# STM32_ADC.net
KiCad netlist of a schematic drawn in Altium Designer
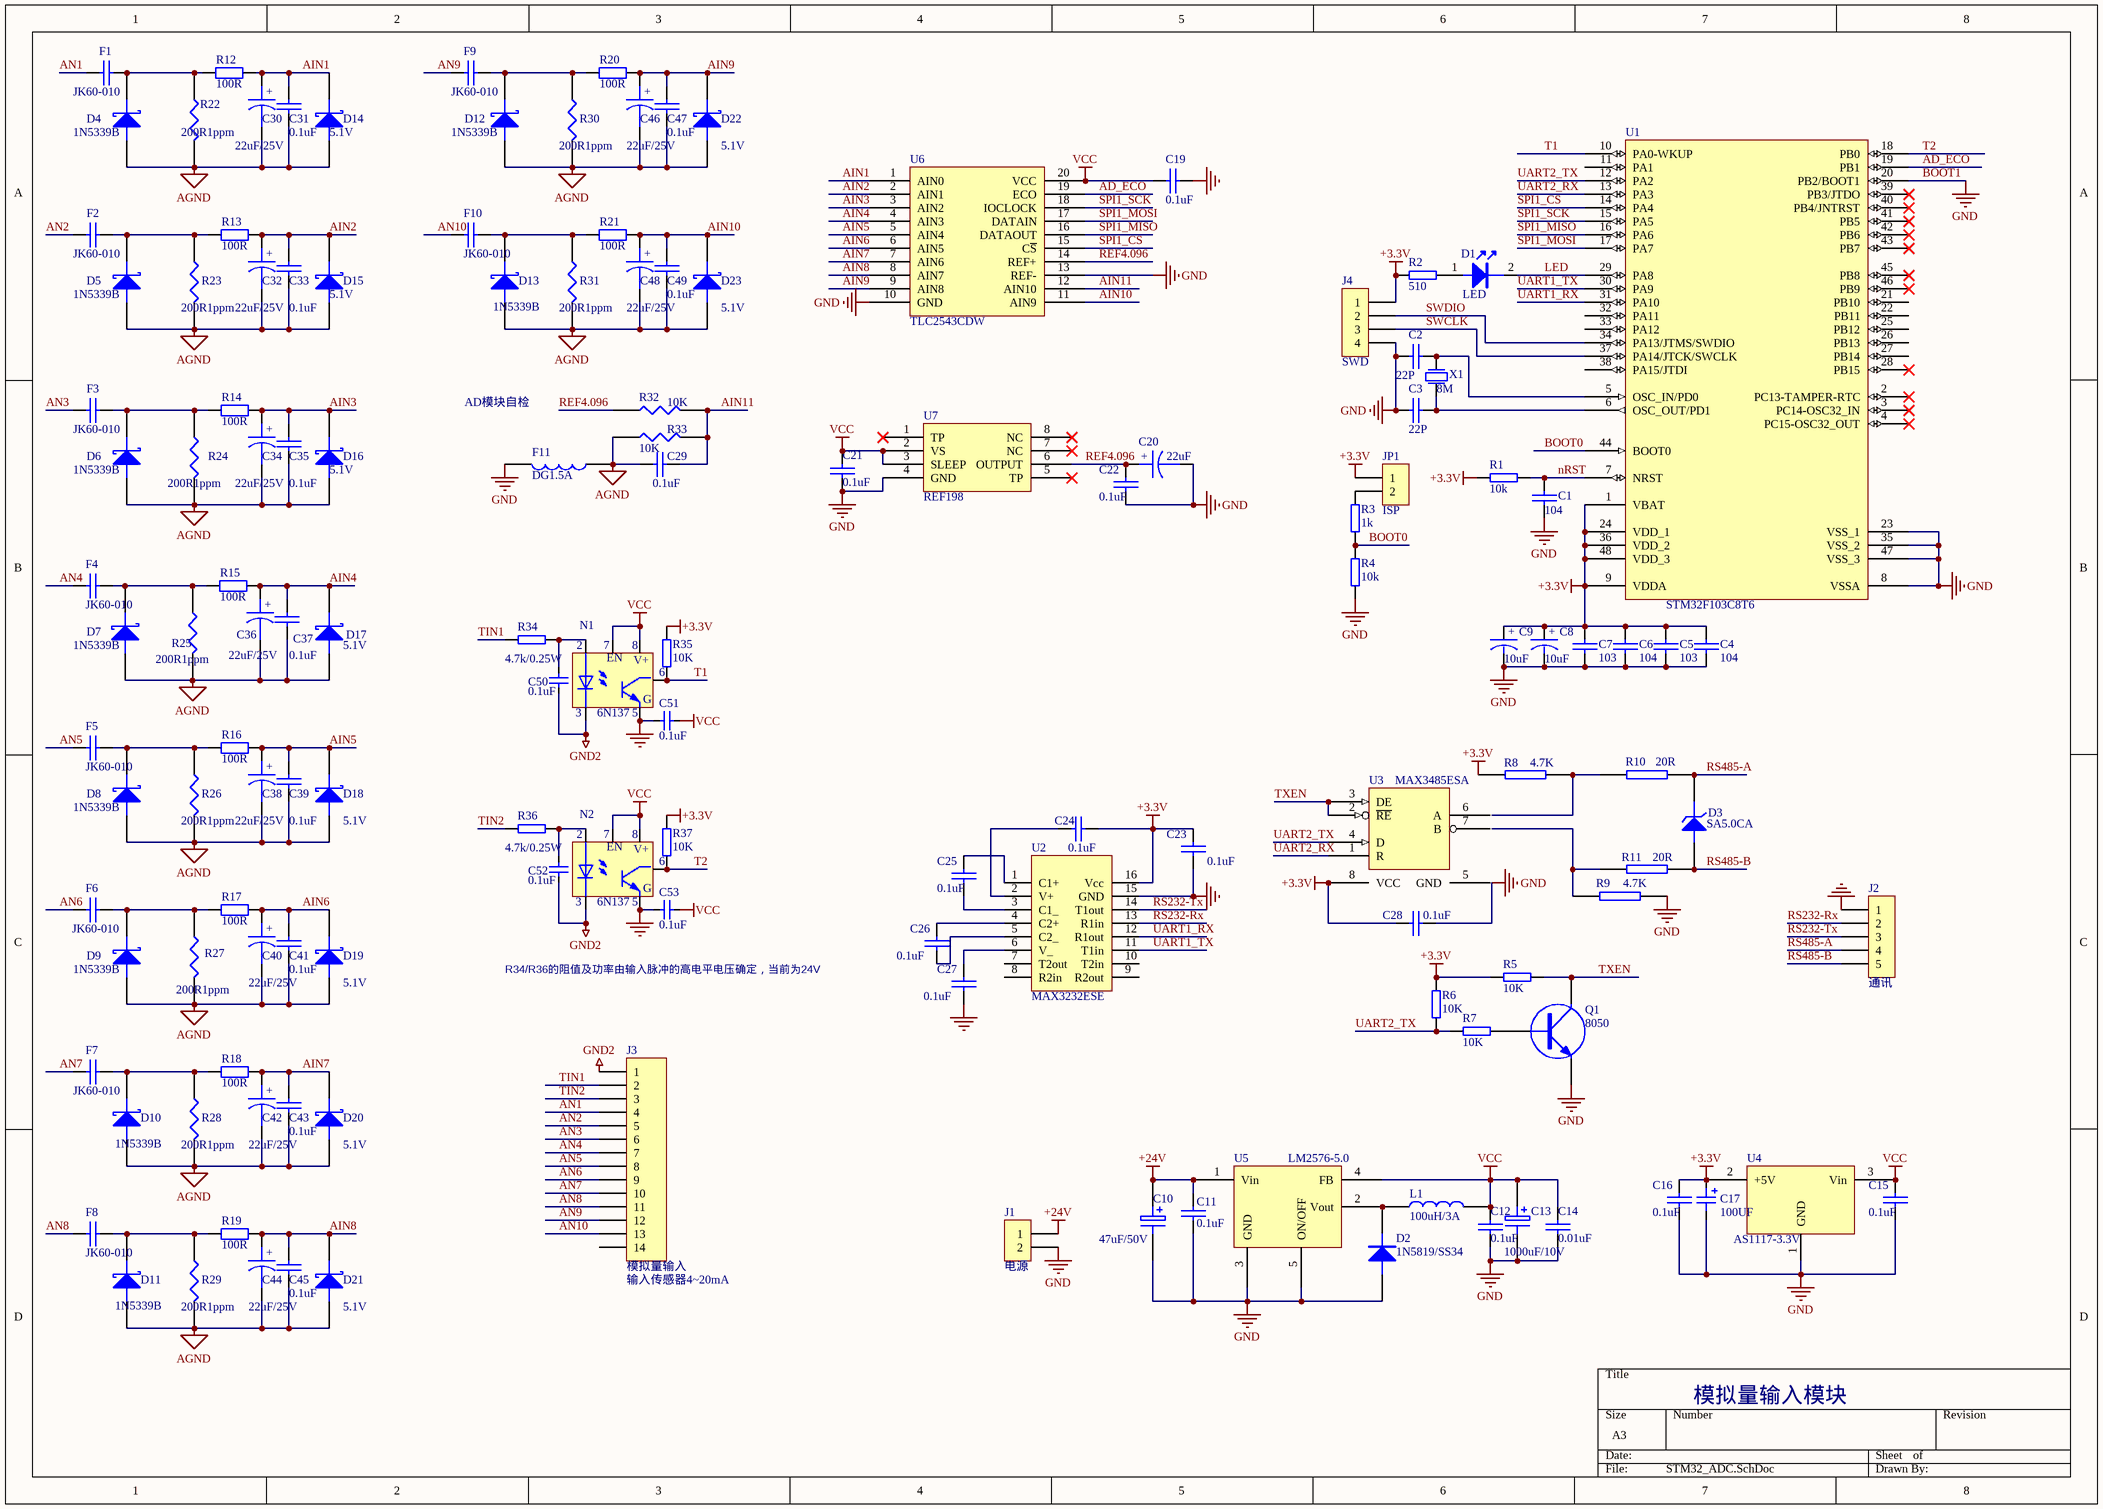
[diagram p0: STM32_ADC.SchDoc]

(export (version "E")
  (design (tool "Eeschema 10.0.6"))
  (components
    (comp (ref "C1")
      (value "104")
      (footprint "0805")
      (description "Capacitor")
      (libsource (lib "") (part "CAP_2"))
    )
    (comp (ref "C2")
      (value "22P")
      (footprint "0805")
      (description "Capacitor")
      (libsource (lib "*") (part "CAP"))
    )
    (comp (ref "C3")
      (value "22P")
      (footprint "0805")
      (description "Capacitor")
      (libsource (lib "*") (part "CAP"))
    )
    (comp (ref "C4")
      (value "104")
      (footprint "0805")
      (description "Capacitor")
      (libsource (lib "") (part "CAP_2"))
    )
    (comp (ref "C5")
      (value "103")
      (footprint "0805")
      (description "Capacitor")
      (libsource (lib "") (part "CAP_2"))
    )
    (comp (ref "C6")
      (value "104")
      (footprint "0805")
      (description "Capacitor")
      (libsource (lib "") (part "CAP_2"))
    )
    (comp (ref "C7")
      (value "103")
      (footprint "0805")
      (description "Capacitor")
      (libsource (lib "") (part "CAP_2"))
    )
    (comp (ref "C8")
      (value "10uF")
      (footprint "1210(+)")
      (description "Capacitor")
      (libsource (lib "2400原理图库") (part "CAPACITOR POL_1"))
    )
    (comp (ref "C9")
      (value "10uF")
      (footprint "1210(+)")
      (description "Capacitor")
      (libsource (lib "2400原理图库") (part "CAPACITOR POL_1"))
    )
    (comp (ref "C10")
      (value "47uF/50V")
      (footprint "ROND-0.2")
      (description "Electrolytic Capacitor")
      (libsource (lib "*") (part "ELECTRO1"))
    )
    (comp (ref "C11")
      (value "0.1uF")
      (footprint "0805")
      (description "Capacitor")
      (libsource (lib "") (part "CAP_1"))
    )
    (comp (ref "C12")
      (value "0.1uF")
      (footprint "0805")
      (description "Capacitor")
      (libsource (lib "") (part "CAP_1"))
    )
    (comp (ref "C13")
      (value "1000uF/10V")
      (footprint "DR10*10")
      (description "Electrolytic Capacitor")
      (libsource (lib "*") (part "ELECTRO1"))
    )
    (comp (ref "C14")
      (value "0.01uF")
      (footprint "0805")
      (description "Capacitor")
      (libsource (lib "") (part "CAP_1"))
    )
    (comp (ref "C15")
      (value "0.1uF")
      (footprint "0805")
      (description "Capacitor")
      (libsource (lib "*") (part "CAP"))
    )
    (comp (ref "C16")
      (value "0.1uF")
      (footprint "0805")
      (description "Capacitor")
      (libsource (lib "*") (part "CAP"))
    )
    (comp (ref "C17") (value "100UF") (footprint "2220-1") (libsource (lib "*") (part "CD")))
    (comp (ref "C19")
      (value "0.1uF")
      (footprint "0805")
      (description "Capacitor")
      (libsource (lib "*") (part "CAP"))
    )
    (comp (ref "C20")
      (value "22uF")
      (footprint "1210(+)")
      (description "Capacitor")
      (libsource (lib "*") (part "CAPACITOR POL"))
    )
    (comp (ref "C21")
      (value "0.1uF")
      (footprint "0805")
      (description "Capacitor")
      (libsource (lib "*") (part "CAP"))
    )
    (comp (ref "C22")
      (value "0.1uF")
      (footprint "0805")
      (description "Capacitor")
      (libsource (lib "*") (part "CAP"))
    )
    (comp (ref "C23")
      (value "0.1uF")
      (footprint "0805")
      (description "Capacitor")
      (libsource (lib "*") (part "CAP"))
    )
    (comp (ref "C24")
      (value "0.1uF")
      (footprint "0805")
      (description "Capacitor")
      (libsource (lib "*") (part "CAP"))
    )
    (comp (ref "C25")
      (value "0.1uF")
      (footprint "0805")
      (description "Capacitor")
      (libsource (lib "*") (part "CAP"))
    )
    (comp (ref "C26")
      (value "0.1uF")
      (footprint "0805")
      (description "Capacitor")
      (libsource (lib "*") (part "CAP"))
    )
    (comp (ref "C27")
      (value "0.1uF")
      (footprint "0805")
      (description "Capacitor")
      (libsource (lib "*") (part "CAP"))
    )
    (comp (ref "C28")
      (value "0.1uF")
      (footprint "0805")
      (description "Capacitor")
      (libsource (lib "*") (part "CAP"))
    )
    (comp (ref "C29")
      (value "0.1uF")
      (footprint "0805")
      (description "Capacitor")
      (libsource (lib "*") (part "CAP"))
    )
    (comp (ref "C30")
      (value "22uF/25V")
      (footprint "1210(+)")
      (description "Capacitor")
      (libsource (lib "*") (part "CAPACITOR POL"))
    )
    (comp (ref "C31")
      (value "0.1uF")
      (footprint "0805")
      (description "Capacitor")
      (libsource (lib "*") (part "CAP"))
    )
    (comp (ref "C32")
      (value "22uF/25V")
      (footprint "1210(+)")
      (description "Capacitor")
      (libsource (lib "*") (part "CAPACITOR POL"))
    )
    (comp (ref "C33")
      (value "0.1uF")
      (footprint "0805")
      (description "Capacitor")
      (libsource (lib "*") (part "CAP"))
    )
    (comp (ref "C34")
      (value "22uF/25V")
      (footprint "1210(+)")
      (description "Capacitor")
      (libsource (lib "*") (part "CAPACITOR POL"))
    )
    (comp (ref "C35")
      (value "0.1uF")
      (footprint "0805")
      (description "Capacitor")
      (libsource (lib "*") (part "CAP"))
    )
    (comp (ref "C36")
      (value "22uF/25V")
      (footprint "1210(+)")
      (description "Capacitor")
      (libsource (lib "*") (part "CAPACITOR POL"))
    )
    (comp (ref "C37")
      (value "0.1uF")
      (footprint "0805")
      (description "Capacitor")
      (libsource (lib "*") (part "CAP"))
    )
    (comp (ref "C38")
      (value "22uF/25V")
      (footprint "1210(+)")
      (description "Capacitor")
      (libsource (lib "*") (part "CAPACITOR POL"))
    )
    (comp (ref "C39")
      (value "0.1uF")
      (footprint "0805")
      (description "Capacitor")
      (libsource (lib "*") (part "CAP"))
    )
    (comp (ref "C40")
      (value "22uF/25V")
      (footprint "1210(+)")
      (description "Capacitor")
      (libsource (lib "*") (part "CAPACITOR POL"))
    )
    (comp (ref "C41")
      (value "0.1uF")
      (footprint "0805")
      (description "Capacitor")
      (libsource (lib "*") (part "CAP"))
    )
    (comp (ref "C42")
      (value "22uF/25V")
      (footprint "1210(+)")
      (description "Capacitor")
      (libsource (lib "*") (part "CAPACITOR POL"))
    )
    (comp (ref "C43")
      (value "0.1uF")
      (footprint "0805")
      (description "Capacitor")
      (libsource (lib "*") (part "CAP"))
    )
    (comp (ref "C44")
      (value "22uF/25V")
      (footprint "1210(+)")
      (description "Capacitor")
      (libsource (lib "*") (part "CAPACITOR POL"))
    )
    (comp (ref "C45")
      (value "0.1uF")
      (footprint "0805")
      (description "Capacitor")
      (libsource (lib "*") (part "CAP"))
    )
    (comp (ref "C46")
      (value "22uF/25V")
      (footprint "1210(+)")
      (description "Capacitor")
      (libsource (lib "*") (part "CAPACITOR POL"))
    )
    (comp (ref "C47")
      (value "0.1uF")
      (footprint "0805")
      (description "Capacitor")
      (libsource (lib "*") (part "CAP"))
    )
    (comp (ref "C48")
      (value "22uF/25V")
      (footprint "1210(+)")
      (description "Capacitor")
      (libsource (lib "*") (part "CAPACITOR POL"))
    )
    (comp (ref "C49")
      (value "0.1uF")
      (footprint "0805")
      (description "Capacitor")
      (libsource (lib "*") (part "CAP"))
    )
    (comp (ref "C50") (value "0.1uF") (footprint "0805") (libsource (lib "*") (part "C")))
    (comp (ref "C51") (value "0.1uF") (footprint "0805") (libsource (lib "*") (part "C")))
    (comp (ref "C52") (value "0.1uF") (footprint "0805") (libsource (lib "*") (part "C")))
    (comp (ref "C53") (value "0.1uF") (footprint "0805") (libsource (lib "*") (part "C")))
    (comp (ref "D1") (value "LED") (footprint "0805") (libsource (lib "pro1") (part "LED")))
    (comp (ref "D2")
      (value "1N5819/SS34")
      (footprint "DIODE-2")
      (description "Diode")
      (libsource (lib "*") (part "DIODE"))
    )
    (comp (ref "D3")
      (value "SA5.0CA")
      (footprint "CON2_4A7")
      (description "Zener Diode")
      (libsource (lib "*") (part "ZENER3"))
    )
    (comp (ref "D4")
      (value "1N5339B")
      (footprint "DIODE-0.3")
      (description "Schottky Diode")
      (libsource (lib "*") (part "DIODE SCHOTTKY"))
    )
    (comp (ref "D5")
      (value "1N5339B")
      (footprint "DIODE-0.3")
      (description "Schottky Diode")
      (libsource (lib "*") (part "DIODE SCHOTTKY"))
    )
    (comp (ref "D6")
      (value "1N5339B")
      (footprint "DIODE-0.3")
      (description "Schottky Diode")
      (libsource (lib "*") (part "DIODE SCHOTTKY"))
    )
    (comp (ref "D7")
      (value "1N5339B")
      (footprint "DIODE-0.3")
      (description "Schottky Diode")
      (libsource (lib "*") (part "DIODE SCHOTTKY"))
    )
    (comp (ref "D8")
      (value "1N5339B")
      (footprint "DIODE-0.3")
      (description "Schottky Diode")
      (libsource (lib "*") (part "DIODE SCHOTTKY"))
    )
    (comp (ref "D9")
      (value "1N5339B")
      (footprint "DIODE-0.3")
      (description "Schottky Diode")
      (libsource (lib "*") (part "DIODE SCHOTTKY"))
    )
    (comp (ref "D10")
      (value "1N5339B")
      (footprint "DIODE-0.3")
      (description "Schottky Diode")
      (libsource (lib "*") (part "DIODE SCHOTTKY"))
    )
    (comp (ref "D11")
      (value "1N5339B")
      (footprint "DIODE-0.3")
      (description "Schottky Diode")
      (libsource (lib "*") (part "DIODE SCHOTTKY"))
    )
    (comp (ref "D12")
      (value "1N5339B")
      (footprint "DIODE-0.3")
      (description "Schottky Diode")
      (libsource (lib "*") (part "DIODE SCHOTTKY"))
    )
    (comp (ref "D13")
      (value "1N5339B")
      (footprint "DIODE-0.3")
      (description "Schottky Diode")
      (libsource (lib "*") (part "DIODE SCHOTTKY"))
    )
    (comp (ref "D14")
      (value "5.1V")
      (footprint "DIDO")
      (description "Schottky Diode")
      (libsource (lib "*") (part "DIODE SCHOTTKY"))
    )
    (comp (ref "D15")
      (value "5.1V")
      (footprint "DIDO")
      (description "Schottky Diode")
      (libsource (lib "*") (part "DIODE SCHOTTKY"))
    )
    (comp (ref "D16")
      (value "5.1V")
      (footprint "DIDO")
      (description "Schottky Diode")
      (libsource (lib "*") (part "DIODE SCHOTTKY"))
    )
    (comp (ref "D17")
      (value "5.1V")
      (footprint "DIDO")
      (description "Schottky Diode")
      (libsource (lib "*") (part "DIODE SCHOTTKY"))
    )
    (comp (ref "D18")
      (value "5.1V")
      (footprint "DIDO")
      (description "Schottky Diode")
      (libsource (lib "*") (part "DIODE SCHOTTKY"))
    )
    (comp (ref "D19")
      (value "5.1V")
      (footprint "DIDO")
      (description "Schottky Diode")
      (libsource (lib "*") (part "DIODE SCHOTTKY"))
    )
    (comp (ref "D20")
      (value "5.1V")
      (footprint "DIDO")
      (description "Schottky Diode")
      (libsource (lib "*") (part "DIODE SCHOTTKY"))
    )
    (comp (ref "D21")
      (value "5.1V")
      (footprint "DIDO")
      (description "Schottky Diode")
      (libsource (lib "*") (part "DIODE SCHOTTKY"))
    )
    (comp (ref "D22")
      (value "5.1V")
      (footprint "DIDO")
      (description "Schottky Diode")
      (libsource (lib "*") (part "DIODE SCHOTTKY"))
    )
    (comp (ref "D23")
      (value "5.1V")
      (footprint "DIDO")
      (description "Schottky Diode")
      (libsource (lib "*") (part "DIODE SCHOTTKY"))
    )
    (comp (ref "F1")
      (value "JK60-010")
      (footprint "RAD0.1")
      (description "Capacitor")
      (libsource (lib "*") (part "CAP"))
    )
    (comp (ref "F2")
      (value "JK60-010")
      (footprint "RAD0.1")
      (description "Capacitor")
      (libsource (lib "*") (part "CAP"))
    )
    (comp (ref "F3")
      (value "JK60-010")
      (footprint "RAD0.1")
      (description "Capacitor")
      (libsource (lib "*") (part "CAP"))
    )
    (comp (ref "F4")
      (value "JK60-010")
      (footprint "RAD0.1")
      (description "Capacitor")
      (libsource (lib "*") (part "CAP"))
    )
    (comp (ref "F5")
      (value "JK60-010")
      (footprint "RAD0.1")
      (description "Capacitor")
      (libsource (lib "*") (part "CAP"))
    )
    (comp (ref "F6")
      (value "JK60-010")
      (footprint "RAD0.1")
      (description "Capacitor")
      (libsource (lib "*") (part "CAP"))
    )
    (comp (ref "F7")
      (value "JK60-010")
      (footprint "RAD0.1")
      (description "Capacitor")
      (libsource (lib "*") (part "CAP"))
    )
    (comp (ref "F8")
      (value "JK60-010")
      (footprint "RAD0.1")
      (description "Capacitor")
      (libsource (lib "*") (part "CAP"))
    )
    (comp (ref "F9")
      (value "JK60-010")
      (footprint "RAD0.1")
      (description "Capacitor")
      (libsource (lib "*") (part "CAP"))
    )
    (comp (ref "F10")
      (value "JK60-010")
      (footprint "RAD0.1")
      (description "Capacitor")
      (libsource (lib "*") (part "CAP"))
    )
    (comp (ref "F11") (value "DG1.5A") (footprint "0805") (libsource (lib "*") (part "INDUCTOR1")))
    (comp (ref "J1")
      (value "电源")
      (footprint "CON2_5.08")
      (description "Connector")
      (libsource (lib "") (part "CON2_1"))
    )
    (comp (ref "J2")
      (value "通讯")
      (footprint "con5")
      (description "Connector")
      (libsource (lib "pro1") (part "CON5"))
    )
    (comp (ref "J3") (value "模拟量输入") (libsource (lib "pro1") (part "CON14")))
    (comp (ref "J4")
      (value "SWD")
      (footprint "CON4")
      (description "Connector")
      (libsource (lib "*") (part "CON4"))
    )
    (comp (ref "JP1")
      (value "ISP")
      (footprint "CON2_2")
      (description "Connector")
      (libsource (lib "pro1") (part "CON2"))
    )
    (comp (ref "L1") (value "100uH/3A") (footprint "DIANGAN1.5A") (libsource (lib "") (part "INDUCTOR1_1")))
    (comp (ref "N1") (value "6N137") (footprint "DIP8") (libsource (lib "*") (part "6N137")))
    (comp (ref "N2") (value "6N137") (footprint "DIP8") (libsource (lib "*") (part "6N137")))
    (comp (ref "Q1")
      (value "8050")
      (footprint "sot-23")
      (description "NPN Transistor")
      (libsource (lib "*") (part "NPN"))
    )
    (comp (ref "R1") (value "10k") (footprint "0805") (libsource (lib "") (part "RES1_1")))
    (comp (ref "R2") (value "510") (footprint "0805") (libsource (lib "") (part "RES1_1")))
    (comp (ref "R3") (value "1k") (footprint "0805") (libsource (lib "") (part "RES1_1")))
    (comp (ref "R4") (value "10k") (footprint "0805") (libsource (lib "") (part "RES1_1")))
    (comp (ref "R5") (value "10K") (footprint "0805") (libsource (lib "") (part "R_1")))
    (comp (ref "R6") (value "10K") (footprint "0805") (libsource (lib "") (part "RES1_1")))
    (comp (ref "R7") (value "10K") (footprint "0805") (libsource (lib "") (part "R_1")))
    (comp (ref "R8") (value "4.7K") (footprint "0805") (libsource (lib "*") (part "RES2")))
    (comp (ref "R9") (value "4.7K") (footprint "0805") (libsource (lib "*") (part "RES2")))
    (comp (ref "R10") (value "20R") (footprint "0805") (libsource (lib "*") (part "RES2")))
    (comp (ref "R11") (value "20R") (footprint "0805") (libsource (lib "*") (part "RES2")))
    (comp (ref "R12")
      (value "100R")
      (footprint "0805")
      (description "Resistor")
      (fields (field (name "PUBLISHER") "*"))
      (libsource (lib "*") (part "Res2"))
    )
    (comp (ref "R13")
      (value "100R")
      (footprint "0805")
      (description "Resistor")
      (fields (field (name "PUBLISHER") "*"))
      (libsource (lib "*") (part "Res2"))
    )
    (comp (ref "R14")
      (value "100R")
      (footprint "0805")
      (description "Resistor")
      (fields (field (name "PUBLISHER") "*"))
      (libsource (lib "*") (part "Res2"))
    )
    (comp (ref "R15")
      (value "100R")
      (footprint "0805")
      (description "Resistor")
      (fields (field (name "PUBLISHER") "*"))
      (libsource (lib "*") (part "Res2"))
    )
    (comp (ref "R16")
      (value "100R")
      (footprint "0805")
      (description "Resistor")
      (fields (field (name "PUBLISHER") "*"))
      (libsource (lib "*") (part "Res2"))
    )
    (comp (ref "R17")
      (value "100R")
      (footprint "0805")
      (description "Resistor")
      (fields (field (name "PUBLISHER") "*"))
      (libsource (lib "*") (part "Res2"))
    )
    (comp (ref "R18")
      (value "100R")
      (footprint "0805")
      (description "Resistor")
      (fields (field (name "PUBLISHER") "*"))
      (libsource (lib "*") (part "Res2"))
    )
    (comp (ref "R19")
      (value "100R")
      (footprint "0805")
      (description "Resistor")
      (fields (field (name "PUBLISHER") "*"))
      (libsource (lib "*") (part "Res2"))
    )
    (comp (ref "R20")
      (value "100R")
      (footprint "0805")
      (description "Resistor")
      (fields (field (name "PUBLISHER") "*"))
      (libsource (lib "*") (part "Res2"))
    )
    (comp (ref "R21")
      (value "100R")
      (footprint "0805")
      (description "Resistor")
      (fields (field (name "PUBLISHER") "*"))
      (libsource (lib "*") (part "Res2"))
    )
    (comp (ref "R22") (value "200R1ppm") (footprint "axial0.3") (libsource (lib "*") (part "RES1")))
    (comp (ref "R23") (value "200R1ppm") (footprint "axial0.3") (libsource (lib "*") (part "RES1")))
    (comp (ref "R24") (value "200R1ppm") (footprint "axial0.3") (libsource (lib "*") (part "RES1")))
    (comp (ref "R25") (value "200R1ppm") (footprint "axial0.3") (libsource (lib "*") (part "RES1")))
    (comp (ref "R26") (value "200R1ppm") (footprint "axial0.3") (libsource (lib "*") (part "RES1")))
    (comp (ref "R27") (value "200R1ppm") (footprint "axial0.3") (libsource (lib "*") (part "RES1")))
    (comp (ref "R28") (value "200R1ppm") (footprint "axial0.3") (libsource (lib "*") (part "RES1")))
    (comp (ref "R29") (value "200R1ppm") (footprint "axial0.3") (libsource (lib "*") (part "RES1")))
    (comp (ref "R30") (value "200R1ppm") (footprint "axial0.3") (libsource (lib "*") (part "RES1")))
    (comp (ref "R31") (value "200R1ppm") (footprint "axial0.3") (libsource (lib "*") (part "RES1")))
    (comp (ref "R32") (value "10K") (footprint "0805") (libsource (lib "*") (part "RES1")))
    (comp (ref "R33") (value "10K") (footprint "0805") (libsource (lib "*") (part "RES1")))
    (comp (ref "R34") (value "4.7k/0.25W") (footprint "0805") (libsource (lib "*") (part "R")))
    (comp (ref "R35") (value "10K") (footprint "0805") (libsource (lib "*") (part "R")))
    (comp (ref "R36") (value "4.7k/0.25W") (footprint "0805") (libsource (lib "*") (part "R")))
    (comp (ref "R37") (value "10K") (footprint "0805") (libsource (lib "*") (part "R")))
    (comp (ref "U1")
      (value "STM32F103C8T6")
      (footprint "STM32F103C-48")
      (description "STM32 ARM-based 32-bit MCU with 64 Kbytes Flash, 48-pin LQFP, Industrial Temperature")
      (fields (field (name "PUBLISHER") "*"))
      (libsource (lib "ST Microcontroller 32-Bit STM32 SCH") (part "STM32F101C8T6"))
    )
    (comp (ref "U2")
      (value "MAX3232ESE")
      (footprint "SO-16")
      (description "Connector")
      (libsource (lib "*") (part "CON16"))
    )
    (comp (ref "U3")
      (value "MAX3485ESA")
      (footprint "SO-8")
      (description "DIFFERENTIAL BUS TRANSCEIVERS")
      (libsource (lib "*") (part "DS36F95"))
    )
    (comp (ref "U4") (value "AS1117-3.3V") (footprint "sot223") (libsource (lib "*") (part "MC79L05CG")))
    (comp (ref "U5") (value "LM2576-5.0") (footprint "TO-220-5S") (libsource (lib "*") (part "LM2576")))
    (comp (ref "U6") (value "TLC2543CDW") (footprint "SOL-20") (libsource (lib "*") (part "TCL2543")))
    (comp (ref "U7") (value "REF198") (footprint "SO-8") (libsource (lib "*") (part "Component_1")))
    (comp (ref "X1")
      (value "8M")
      (footprint "XATL-5MM")
      (description "Crystal Oscillator")
      (libsource (lib "*") (part "12M"))
    )
  )
  (nets
    (net (code "1") (name "+3.3V") (class "Default")
      (node (ref "C12") (pin "1") (pinfunction "1_1") (pintype "passive"))
      (node (ref "C13") (pin "1") (pinfunction "1_1") (pintype "passive"))
      (node (ref "C14") (pin "2") (pinfunction "2_2") (pintype "passive"))
      (node (ref "C15") (pin "2") (pinfunction "2_2") (pintype "passive"))
      (node (ref "C16") (pin "2") (pinfunction "2_2") (pintype "passive"))
      (node (ref "C17") (pin "1") (pintype "passive"))
      (node (ref "C19") (pin "1") (pinfunction "1_1") (pintype "passive"))
      (node (ref "C21") (pin "1") (pinfunction "1_1") (pintype "passive"))
      (node (ref "C23") (pin "1") (pinfunction "1_1") (pintype "passive"))
      (node (ref "C24") (pin "2") (pinfunction "2_2") (pintype "passive"))
      (node (ref "C28") (pin "1") (pinfunction "1_1") (pintype "passive"))
      (node (ref "C4") (pin "1") (pinfunction "1_1") (pintype "passive"))
      (node (ref "C5") (pin "1") (pinfunction "1_1") (pintype "passive"))
      (node (ref "C51") (pin "1") (pintype "passive"))
      (node (ref "C53") (pin "1") (pintype "passive"))
      (node (ref "C6") (pin "1") (pinfunction "1_1") (pintype "passive"))
      (node (ref "C7") (pin "1") (pinfunction "1_1") (pintype "passive"))
      (node (ref "C8") (pin "1") (pinfunction "1_1") (pintype "passive"))
      (node (ref "C9") (pin "1") (pinfunction "1_1") (pintype "passive"))
      (node (ref "J4") (pin "1") (pinfunction "1_1") (pintype "passive"))
      (node (ref "JP1") (pin "1") (pinfunction "1_1") (pintype "passive"))
      (node (ref "L1") (pin "2") (pinfunction "2_2") (pintype "passive"))
      (node (ref "N1") (pin "7") (pinfunction "EN_7") (pintype "passive"))
      (node (ref "N1") (pin "8") (pinfunction "VCC_8") (pintype "passive"))
      (node (ref "N2") (pin "7") (pinfunction "EN_7") (pintype "passive"))
      (node (ref "N2") (pin "8") (pinfunction "VCC_8") (pintype "passive"))
      (node (ref "R1") (pin "1") (pintype "passive"))
      (node (ref "R2") (pin "1") (pintype "passive"))
      (node (ref "R35") (pin "2") (pintype "passive"))
      (node (ref "R37") (pin "2") (pintype "passive"))
      (node (ref "R5") (pin "1") (pintype "passive"))
      (node (ref "R6") (pin "1") (pintype "passive"))
      (node (ref "R8") (pin "2") (pinfunction "2_2") (pintype "passive"))
      (node (ref "U1") (pin "1") (pinfunction "VBAT_1") (pintype "power_in"))
      (node (ref "U1") (pin "24") (pinfunction "VDD_1_24") (pintype "power_in"))
      (node (ref "U1") (pin "36") (pinfunction "VDD_2_36") (pintype "power_in"))
      (node (ref "U1") (pin "48") (pinfunction "VDD_3_48") (pintype "power_in"))
      (node (ref "U1") (pin "9") (pinfunction "VDDA_9") (pintype "power_in"))
      (node (ref "U2") (pin "16") (pinfunction "Vcc_16") (pintype "passive"))
      (node (ref "U3") (pin "8") (pinfunction "VCC_8") (pintype "power_in"))
      (node (ref "U4") (pin "2") (pinfunction "+5V_2") (pintype "passive"))
      (node (ref "U4") (pin "3") (pinfunction "Vin_3") (pintype "passive"))
      (node (ref "U5") (pin "4") (pinfunction "FB_4") (pintype "passive"))
      (node (ref "U6") (pin "20") (pinfunction "VCC_20") (pintype "passive"))
      (node (ref "U7") (pin "2") (pinfunction "VS_2") (pintype "passive"))
      (node (ref "U7") (pin "3") (pinfunction "SLEEP_3") (pintype "passive"))
    )
    (net (code "2") (name "+24V") (class "Default")
      (node (ref "C10") (pin "1") (pinfunction "1_1") (pintype "passive"))
      (node (ref "C11") (pin "2") (pinfunction "2_2") (pintype "passive"))
      (node (ref "J1") (pin "1") (pinfunction "1_1") (pintype "passive"))
      (node (ref "U5") (pin "1") (pinfunction "Vin_1") (pintype "passive"))
    )
    (net (code "3") (name "/AD_ECO") (class "Default")
      (node (ref "U1") (pin "19") (pinfunction "PB1_19") (pintype "bidirectional"))
      (node (ref "U6") (pin "19") (pinfunction "ECO_19") (pintype "passive"))
    )
    (net (code "4") (name "/AIN1") (class "Default")
      (node (ref "C30") (pin "1") (pinfunction "1_1") (pintype "passive"))
      (node (ref "C31") (pin "1") (pinfunction "1_1") (pintype "passive"))
      (node (ref "D14") (pin "2") (pinfunction "K_2") (pintype "passive"))
      (node (ref "R12") (pin "2") (pinfunction "2_2") (pintype "passive"))
      (node (ref "U6") (pin "1") (pinfunction "AIN0_1") (pintype "passive"))
    )
    (net (code "5") (name "/AIN2") (class "Default")
      (node (ref "C32") (pin "1") (pinfunction "1_1") (pintype "passive"))
      (node (ref "C33") (pin "1") (pinfunction "1_1") (pintype "passive"))
      (node (ref "D15") (pin "2") (pinfunction "K_2") (pintype "passive"))
      (node (ref "R13") (pin "2") (pinfunction "2_2") (pintype "passive"))
      (node (ref "U6") (pin "2") (pinfunction "AIN1_2") (pintype "passive"))
    )
    (net (code "6") (name "/AIN3") (class "Default")
      (node (ref "C34") (pin "1") (pinfunction "1_1") (pintype "passive"))
      (node (ref "C35") (pin "1") (pinfunction "1_1") (pintype "passive"))
      (node (ref "D16") (pin "2") (pinfunction "K_2") (pintype "passive"))
      (node (ref "R14") (pin "2") (pinfunction "2_2") (pintype "passive"))
      (node (ref "U6") (pin "3") (pinfunction "AIN2_3") (pintype "passive"))
    )
    (net (code "7") (name "/AIN4") (class "Default")
      (node (ref "C36") (pin "1") (pinfunction "1_1") (pintype "passive"))
      (node (ref "C37") (pin "1") (pinfunction "1_1") (pintype "passive"))
      (node (ref "D17") (pin "2") (pinfunction "K_2") (pintype "passive"))
      (node (ref "R15") (pin "2") (pinfunction "2_2") (pintype "passive"))
      (node (ref "U6") (pin "4") (pinfunction "AIN3_4") (pintype "passive"))
    )
    (net (code "8") (name "/AIN5") (class "Default")
      (node (ref "C38") (pin "1") (pinfunction "1_1") (pintype "passive"))
      (node (ref "C39") (pin "1") (pinfunction "1_1") (pintype "passive"))
      (node (ref "D18") (pin "2") (pinfunction "K_2") (pintype "passive"))
      (node (ref "R16") (pin "2") (pinfunction "2_2") (pintype "passive"))
      (node (ref "U6") (pin "5") (pinfunction "AIN4_5") (pintype "passive"))
    )
    (net (code "9") (name "/AIN6") (class "Default")
      (node (ref "C40") (pin "1") (pinfunction "1_1") (pintype "passive"))
      (node (ref "C41") (pin "1") (pinfunction "1_1") (pintype "passive"))
      (node (ref "D19") (pin "2") (pinfunction "K_2") (pintype "passive"))
      (node (ref "R17") (pin "2") (pinfunction "2_2") (pintype "passive"))
      (node (ref "U6") (pin "6") (pinfunction "AIN5_6") (pintype "passive"))
    )
    (net (code "10") (name "/AIN7") (class "Default")
      (node (ref "C42") (pin "1") (pinfunction "1_1") (pintype "passive"))
      (node (ref "C43") (pin "1") (pinfunction "1_1") (pintype "passive"))
      (node (ref "D20") (pin "2") (pinfunction "K_2") (pintype "passive"))
      (node (ref "R18") (pin "2") (pinfunction "2_2") (pintype "passive"))
      (node (ref "U6") (pin "7") (pinfunction "AIN6_7") (pintype "passive"))
    )
    (net (code "11") (name "/AIN8") (class "Default")
      (node (ref "C44") (pin "1") (pinfunction "1_1") (pintype "passive"))
      (node (ref "C45") (pin "1") (pinfunction "1_1") (pintype "passive"))
      (node (ref "D21") (pin "2") (pinfunction "K_2") (pintype "passive"))
      (node (ref "R19") (pin "2") (pinfunction "2_2") (pintype "passive"))
      (node (ref "U6") (pin "8") (pinfunction "AIN7_8") (pintype "passive"))
    )
    (net (code "12") (name "/AIN9") (class "Default")
      (node (ref "C46") (pin "1") (pinfunction "1_1") (pintype "passive"))
      (node (ref "C47") (pin "1") (pinfunction "1_1") (pintype "passive"))
      (node (ref "D22") (pin "2") (pinfunction "K_2") (pintype "passive"))
      (node (ref "R20") (pin "2") (pinfunction "2_2") (pintype "passive"))
      (node (ref "U6") (pin "9") (pinfunction "AIN8_9") (pintype "passive"))
    )
    (net (code "13") (name "/AIN10") (class "Default")
      (node (ref "C48") (pin "1") (pinfunction "1_1") (pintype "passive"))
      (node (ref "C49") (pin "1") (pinfunction "1_1") (pintype "passive"))
      (node (ref "D23") (pin "2") (pinfunction "K_2") (pintype "passive"))
      (node (ref "R21") (pin "2") (pinfunction "2_2") (pintype "passive"))
      (node (ref "U6") (pin "11") (pinfunction "AIN9_11") (pintype "passive"))
    )
    (net (code "14") (name "/AIN11") (class "Default")
      (node (ref "C29") (pin "2") (pinfunction "2_2") (pintype "passive"))
      (node (ref "R32") (pin "2") (pinfunction "2_2") (pintype "passive"))
      (node (ref "R33") (pin "2") (pinfunction "2_2") (pintype "passive"))
      (node (ref "U6") (pin "12") (pinfunction "AIN10_12") (pintype "passive"))
    )
    (net (code "15") (name "/AN1") (class "Default")
      (node (ref "F1") (pin "1") (pinfunction "1_1") (pintype "passive"))
      (node (ref "J3") (pin "4") (pinfunction "4_4") (pintype "passive"))
    )
    (net (code "16") (name "/AN2") (class "Default")
      (node (ref "F2") (pin "1") (pinfunction "1_1") (pintype "passive"))
      (node (ref "J3") (pin "5") (pinfunction "5_5") (pintype "passive"))
    )
    (net (code "17") (name "/AN3") (class "Default")
      (node (ref "F3") (pin "1") (pinfunction "1_1") (pintype "passive"))
      (node (ref "J3") (pin "6") (pinfunction "6_6") (pintype "passive"))
    )
    (net (code "18") (name "/AN4") (class "Default")
      (node (ref "F4") (pin "1") (pinfunction "1_1") (pintype "passive"))
      (node (ref "J3") (pin "7") (pinfunction "7_7") (pintype "passive"))
    )
    (net (code "19") (name "/AN5") (class "Default")
      (node (ref "F5") (pin "1") (pinfunction "1_1") (pintype "passive"))
      (node (ref "J3") (pin "8") (pinfunction "8_8") (pintype "passive"))
    )
    (net (code "20") (name "/AN6") (class "Default")
      (node (ref "F6") (pin "1") (pinfunction "1_1") (pintype "passive"))
      (node (ref "J3") (pin "9") (pinfunction "9_9") (pintype "passive"))
    )
    (net (code "21") (name "/AN7") (class "Default")
      (node (ref "F7") (pin "1") (pinfunction "1_1") (pintype "passive"))
      (node (ref "J3") (pin "10") (pinfunction "10_10") (pintype "passive"))
    )
    (net (code "22") (name "/AN8") (class "Default")
      (node (ref "F8") (pin "1") (pinfunction "1_1") (pintype "passive"))
      (node (ref "J3") (pin "11") (pinfunction "11_11") (pintype "passive"))
    )
    (net (code "23") (name "/AN9") (class "Default")
      (node (ref "F9") (pin "1") (pinfunction "1_1") (pintype "passive"))
      (node (ref "J3") (pin "12") (pinfunction "12_12") (pintype "passive"))
    )
    (net (code "24") (name "/AN10") (class "Default")
      (node (ref "F10") (pin "1") (pinfunction "1_1") (pintype "passive"))
      (node (ref "J3") (pin "13") (pinfunction "13_13") (pintype "passive"))
    )
    (net (code "25") (name "/BOOT0") (class "Default")
      (node (ref "R3") (pin "2") (pintype "passive"))
      (node (ref "R4") (pin "1") (pintype "passive"))
      (node (ref "U1") (pin "44") (pinfunction "BOOT0_44") (pintype "input"))
    )
    (net (code "26") (name "/LED") (class "Default")
      (node (ref "D1") (pin "2") (pinfunction "K_2") (pintype "passive"))
      (node (ref "U1") (pin "29") (pinfunction "PA8_29") (pintype "bidirectional"))
    )
    (net (code "27") (name "/REF4.096") (class "Default")
      (node (ref "C20") (pin "1") (pinfunction "1_1") (pintype "passive"))
      (node (ref "C22") (pin "1") (pinfunction "1_1") (pintype "passive"))
      (node (ref "R32") (pin "1") (pinfunction "1_1") (pintype "passive"))
      (node (ref "U6") (pin "14") (pinfunction "REF+_14") (pintype "passive"))
      (node (ref "U7") (pin "6") (pinfunction "OUTPUT_6") (pintype "passive"))
    )
    (net (code "28") (name "/RS232-Rx") (class "Default")
      (node (ref "J2") (pin "2") (pinfunction "2_2") (pintype "passive"))
      (node (ref "U2") (pin "13") (pinfunction "R1in_13") (pintype "passive"))
    )
    (net (code "29") (name "/RS232-Tx") (class "Default")
      (node (ref "J2") (pin "3") (pinfunction "3_3") (pintype "passive"))
      (node (ref "U2") (pin "14") (pinfunction "T1out_14") (pintype "passive"))
    )
    (net (code "30") (name "/RS485-A") (class "Default")
      (node (ref "D3") (pin "2") (pinfunction "K_2") (pintype "passive"))
      (node (ref "J2") (pin "4") (pinfunction "4_4") (pintype "passive"))
      (node (ref "R10") (pin "2") (pinfunction "2_2") (pintype "passive"))
    )
    (net (code "31") (name "/RS485-B") (class "Default")
      (node (ref "D3") (pin "1") (pinfunction "A_1") (pintype "passive"))
      (node (ref "J2") (pin "5") (pinfunction "5_5") (pintype "passive"))
      (node (ref "R11") (pin "2") (pinfunction "2_2") (pintype "passive"))
    )
    (net (code "32") (name "/SPI1_CS") (class "Default")
      (node (ref "U1") (pin "14") (pinfunction "PA4_14") (pintype "bidirectional"))
      (node (ref "U6") (pin "15") (pinfunction "C~{S}_15") (pintype "passive"))
    )
    (net (code "33") (name "/SPI1_MISO") (class "Default")
      (node (ref "U1") (pin "16") (pinfunction "PA6_16") (pintype "bidirectional"))
      (node (ref "U6") (pin "16") (pinfunction "DATAOUT_16") (pintype "passive"))
    )
    (net (code "34") (name "/SPI1_MOSI") (class "Default")
      (node (ref "U1") (pin "17") (pinfunction "PA7_17") (pintype "bidirectional"))
      (node (ref "U6") (pin "17") (pinfunction "DATAIN_17") (pintype "passive"))
    )
    (net (code "35") (name "/SPI1_SCK") (class "Default")
      (node (ref "U1") (pin "15") (pinfunction "PA5_15") (pintype "bidirectional"))
      (node (ref "U6") (pin "18") (pinfunction "IOCLOCK_18") (pintype "passive"))
    )
    (net (code "36") (name "/SWCLK") (class "Default")
      (node (ref "J4") (pin "3") (pinfunction "3_3") (pintype "passive"))
      (node (ref "U1") (pin "37") (pinfunction "PA14/JTCK/SWCLK_37") (pintype "bidirectional"))
    )
    (net (code "37") (name "/SWDIO") (class "Default")
      (node (ref "J4") (pin "2") (pinfunction "2_2") (pintype "passive"))
      (node (ref "U1") (pin "34") (pinfunction "PA13/JTMS/SWDIO_34") (pintype "bidirectional"))
    )
    (net (code "38") (name "/T1") (class "Default")
      (node (ref "N1") (pin "6") (pinfunction "OUT_6") (pintype "passive"))
      (node (ref "R35") (pin "1") (pintype "passive"))
      (node (ref "U1") (pin "10") (pinfunction "PA0-WKUP_10") (pintype "bidirectional"))
    )
    (net (code "39") (name "/T2") (class "Default")
      (node (ref "N2") (pin "6") (pinfunction "OUT_6") (pintype "passive"))
      (node (ref "R37") (pin "1") (pintype "passive"))
      (node (ref "U1") (pin "18") (pinfunction "PB0_18") (pintype "bidirectional"))
    )
    (net (code "40") (name "/TIN1") (class "Default")
      (node (ref "J3") (pin "2") (pinfunction "2_2") (pintype "passive"))
      (node (ref "R34") (pin "2") (pintype "passive"))
    )
    (net (code "41") (name "/TIN2") (class "Default")
      (node (ref "J3") (pin "3") (pinfunction "3_3") (pintype "passive"))
      (node (ref "R36") (pin "2") (pintype "passive"))
    )
    (net (code "42") (name "/TXEN") (class "Default")
      (node (ref "Q1") (pin "3") (pinfunction "C_3") (pintype "passive"))
      (node (ref "R5") (pin "2") (pintype "passive"))
      (node (ref "U3") (pin "2") (pinfunction "~{RE}_2") (pintype "input"))
      (node (ref "U3") (pin "3") (pinfunction "DE_3") (pintype "input"))
    )
    (net (code "43") (name "/UART1_RX") (class "Default")
      (node (ref "U1") (pin "31") (pinfunction "PA10_31") (pintype "bidirectional"))
      (node (ref "U2") (pin "12") (pinfunction "R1out_12") (pintype "passive"))
    )
    (net (code "44") (name "/UART1_TX") (class "Default")
      (node (ref "U1") (pin "30") (pinfunction "PA9_30") (pintype "bidirectional"))
      (node (ref "U2") (pin "11") (pinfunction "T1in_11") (pintype "passive"))
    )
    (net (code "45") (name "/UART2_RX") (class "Default")
      (node (ref "U1") (pin "13") (pinfunction "PA3_13") (pintype "bidirectional"))
      (node (ref "U3") (pin "1") (pinfunction "R_1") (pintype "tri_state"))
    )
    (net (code "46") (name "/UART2_TX") (class "Default")
      (node (ref "R6") (pin "2") (pintype "passive"))
      (node (ref "R7") (pin "1") (pintype "passive"))
      (node (ref "U1") (pin "12") (pinfunction "PA2_12") (pintype "bidirectional"))
      (node (ref "U3") (pin "4") (pinfunction "D_4") (pintype "input"))
    )
    (net (code "47") (name "/nRST") (class "Default")
      (node (ref "C1") (pin "2") (pinfunction "2_2") (pintype "passive"))
      (node (ref "R1") (pin "2") (pintype "passive"))
      (node (ref "U1") (pin "7") (pinfunction "NRST_7") (pintype "bidirectional"))
    )
    (net (code "48") (name "AGND") (class "Default")
      (node (ref "C29") (pin "1") (pinfunction "1_1") (pintype "passive"))
      (node (ref "C30") (pin "2") (pinfunction "2_2") (pintype "passive"))
      (node (ref "C31") (pin "2") (pinfunction "2_2") (pintype "passive"))
      (node (ref "C32") (pin "2") (pinfunction "2_2") (pintype "passive"))
      (node (ref "C33") (pin "2") (pinfunction "2_2") (pintype "passive"))
      (node (ref "C34") (pin "2") (pinfunction "2_2") (pintype "passive"))
      (node (ref "C35") (pin "2") (pinfunction "2_2") (pintype "passive"))
      (node (ref "C36") (pin "2") (pinfunction "2_2") (pintype "passive"))
      (node (ref "C37") (pin "2") (pinfunction "2_2") (pintype "passive"))
      (node (ref "C38") (pin "2") (pinfunction "2_2") (pintype "passive"))
      (node (ref "C39") (pin "2") (pinfunction "2_2") (pintype "passive"))
      (node (ref "C40") (pin "2") (pinfunction "2_2") (pintype "passive"))
      (node (ref "C41") (pin "2") (pinfunction "2_2") (pintype "passive"))
      (node (ref "C42") (pin "2") (pinfunction "2_2") (pintype "passive"))
      (node (ref "C43") (pin "2") (pinfunction "2_2") (pintype "passive"))
      (node (ref "C44") (pin "2") (pinfunction "2_2") (pintype "passive"))
      (node (ref "C45") (pin "2") (pinfunction "2_2") (pintype "passive"))
      (node (ref "C46") (pin "2") (pinfunction "2_2") (pintype "passive"))
      (node (ref "C47") (pin "2") (pinfunction "2_2") (pintype "passive"))
      (node (ref "C48") (pin "2") (pinfunction "2_2") (pintype "passive"))
      (node (ref "C49") (pin "2") (pinfunction "2_2") (pintype "passive"))
      (node (ref "D10") (pin "1") (pinfunction "A_1") (pintype "passive"))
      (node (ref "D11") (pin "1") (pinfunction "A_1") (pintype "passive"))
      (node (ref "D12") (pin "1") (pinfunction "A_1") (pintype "passive"))
      (node (ref "D13") (pin "1") (pinfunction "A_1") (pintype "passive"))
      (node (ref "D14") (pin "1") (pinfunction "A_1") (pintype "passive"))
      (node (ref "D15") (pin "1") (pinfunction "A_1") (pintype "passive"))
      (node (ref "D16") (pin "1") (pinfunction "A_1") (pintype "passive"))
      (node (ref "D17") (pin "1") (pinfunction "A_1") (pintype "passive"))
      (node (ref "D18") (pin "1") (pinfunction "A_1") (pintype "passive"))
      (node (ref "D19") (pin "1") (pinfunction "A_1") (pintype "passive"))
      (node (ref "D20") (pin "1") (pinfunction "A_1") (pintype "passive"))
      (node (ref "D21") (pin "1") (pinfunction "A_1") (pintype "passive"))
      (node (ref "D22") (pin "1") (pinfunction "A_1") (pintype "passive"))
      (node (ref "D23") (pin "1") (pinfunction "A_1") (pintype "passive"))
      (node (ref "D4") (pin "1") (pinfunction "A_1") (pintype "passive"))
      (node (ref "D5") (pin "1") (pinfunction "A_1") (pintype "passive"))
      (node (ref "D6") (pin "1") (pinfunction "A_1") (pintype "passive"))
      (node (ref "D7") (pin "1") (pinfunction "A_1") (pintype "passive"))
      (node (ref "D8") (pin "1") (pinfunction "A_1") (pintype "passive"))
      (node (ref "D9") (pin "1") (pinfunction "A_1") (pintype "passive"))
      (node (ref "F11") (pin "1") (pinfunction "1_1") (pintype "passive"))
      (node (ref "R22") (pin "2") (pinfunction "2_2") (pintype "passive"))
      (node (ref "R23") (pin "2") (pinfunction "2_2") (pintype "passive"))
      (node (ref "R24") (pin "2") (pinfunction "2_2") (pintype "passive"))
      (node (ref "R25") (pin "2") (pinfunction "2_2") (pintype "passive"))
      (node (ref "R26") (pin "2") (pinfunction "2_2") (pintype "passive"))
      (node (ref "R27") (pin "2") (pinfunction "2_2") (pintype "passive"))
      (node (ref "R28") (pin "2") (pinfunction "2_2") (pintype "passive"))
      (node (ref "R29") (pin "2") (pinfunction "2_2") (pintype "passive"))
      (node (ref "R30") (pin "2") (pinfunction "2_2") (pintype "passive"))
      (node (ref "R31") (pin "2") (pinfunction "2_2") (pintype "passive"))
      (node (ref "R33") (pin "1") (pinfunction "1_1") (pintype "passive"))
    )
    (net (code "49") (name "GND") (class "Default")
      (node (ref "C1") (pin "1") (pinfunction "1_1") (pintype "passive"))
      (node (ref "C10") (pin "2") (pinfunction "2_2") (pintype "passive"))
      (node (ref "C11") (pin "1") (pinfunction "1_1") (pintype "passive"))
      (node (ref "C12") (pin "2") (pinfunction "2_2") (pintype "passive"))
      (node (ref "C13") (pin "2") (pinfunction "2_2") (pintype "passive"))
      (node (ref "C14") (pin "1") (pinfunction "1_1") (pintype "passive"))
      (node (ref "C15") (pin "1") (pinfunction "1_1") (pintype "passive"))
      (node (ref "C16") (pin "1") (pinfunction "1_1") (pintype "passive"))
      (node (ref "C17") (pin "2") (pintype "passive"))
      (node (ref "C19") (pin "2") (pinfunction "2_2") (pintype "passive"))
      (node (ref "C2") (pin "1") (pinfunction "1_1") (pintype "passive"))
      (node (ref "C20") (pin "2") (pinfunction "2_2") (pintype "passive"))
      (node (ref "C21") (pin "2") (pinfunction "2_2") (pintype "passive"))
      (node (ref "C22") (pin "2") (pinfunction "2_2") (pintype "passive"))
      (node (ref "C23") (pin "2") (pinfunction "2_2") (pintype "passive"))
      (node (ref "C27") (pin "1") (pinfunction "1_1") (pintype "passive"))
      (node (ref "C28") (pin "2") (pinfunction "2_2") (pintype "passive"))
      (node (ref "C3") (pin "1") (pinfunction "1_1") (pintype "passive"))
      (node (ref "C4") (pin "2") (pinfunction "2_2") (pintype "passive"))
      (node (ref "C5") (pin "2") (pinfunction "2_2") (pintype "passive"))
      (node (ref "C51") (pin "2") (pintype "passive"))
      (node (ref "C53") (pin "2") (pintype "passive"))
      (node (ref "C6") (pin "2") (pinfunction "2_2") (pintype "passive"))
      (node (ref "C7") (pin "2") (pinfunction "2_2") (pintype "passive"))
      (node (ref "C8") (pin "2") (pinfunction "2_2") (pintype "passive"))
      (node (ref "C9") (pin "2") (pinfunction "2_2") (pintype "passive"))
      (node (ref "D2") (pin "1") (pinfunction "A_1") (pintype "passive"))
      (node (ref "F11") (pin "2") (pinfunction "2_2") (pintype "passive"))
      (node (ref "J1") (pin "2") (pinfunction "2_2") (pintype "passive"))
      (node (ref "J2") (pin "1") (pinfunction "1_1") (pintype "passive"))
      (node (ref "J4") (pin "4") (pinfunction "4_4") (pintype "passive"))
      (node (ref "N1") (pin "5") (pinfunction "GND_5") (pintype "passive"))
      (node (ref "N2") (pin "5") (pinfunction "GND_5") (pintype "passive"))
      (node (ref "Q1") (pin "2") (pinfunction "E_2") (pintype "passive"))
      (node (ref "R4") (pin "2") (pintype "passive"))
      (node (ref "R9") (pin "2") (pinfunction "2_2") (pintype "passive"))
      (node (ref "U1") (pin "20") (pinfunction "PB2/BOOT1_20") (pintype "bidirectional"))
      (node (ref "U1") (pin "23") (pinfunction "VSS_1_23") (pintype "power_in"))
      (node (ref "U1") (pin "35") (pinfunction "VSS_2_35") (pintype "power_in"))
      (node (ref "U1") (pin "47") (pinfunction "VSS_3_47") (pintype "power_in"))
      (node (ref "U1") (pin "8") (pinfunction "VSSA_8") (pintype "power_in"))
      (node (ref "U2") (pin "15") (pinfunction "GND_15") (pintype "passive"))
      (node (ref "U3") (pin "5") (pinfunction "GND_5") (pintype "power_in"))
      (node (ref "U4") (pin "1") (pinfunction "GND_1") (pintype "passive"))
      (node (ref "U5") (pin "3") (pinfunction "GND_3") (pintype "passive"))
      (node (ref "U5") (pin "5") (pinfunction "ON/OFF_5") (pintype "passive"))
      (node (ref "U6") (pin "10") (pinfunction "GND_10") (pintype "passive"))
      (node (ref "U6") (pin "13") (pinfunction "REF-_13") (pintype "passive"))
      (node (ref "U7") (pin "4") (pinfunction "GND_4") (pintype "passive"))
    )
    (net (code "50") (name "GND2") (class "Default")
      (node (ref "C50") (pin "1") (pintype "passive"))
      (node (ref "C52") (pin "1") (pintype "passive"))
      (node (ref "J3") (pin "1") (pinfunction "1_1") (pintype "passive"))
      (node (ref "N1") (pin "3") (pinfunction "K_3") (pintype "passive"))
      (node (ref "N2") (pin "3") (pinfunction "K_3") (pintype "passive"))
    )
    (net (code "51") (name "Net-(D1-A)") (class "Default")
      (node (ref "D1") (pin "1") (pinfunction "A_1") (pintype "passive"))
      (node (ref "R2") (pin "2") (pintype "passive"))
    )
    (net (code "52") (name "Net-(D2-K)") (class "Default")
      (node (ref "D2") (pin "2") (pinfunction "K_2") (pintype "passive"))
      (node (ref "L1") (pin "1") (pinfunction "1_1") (pintype "passive"))
      (node (ref "U5") (pin "2") (pinfunction "Vout_2") (pintype "passive"))
    )
    (net (code "53") (name "Net-(D4-K)") (class "Default")
      (node (ref "D4") (pin "2") (pinfunction "K_2") (pintype "passive"))
      (node (ref "F1") (pin "2") (pinfunction "2_2") (pintype "passive"))
      (node (ref "R12") (pin "1") (pinfunction "1_1") (pintype "passive"))
      (node (ref "R22") (pin "1") (pinfunction "1_1") (pintype "passive"))
    )
    (net (code "54") (name "Net-(D5-K)") (class "Default")
      (node (ref "D5") (pin "2") (pinfunction "K_2") (pintype "passive"))
      (node (ref "F2") (pin "2") (pinfunction "2_2") (pintype "passive"))
      (node (ref "R13") (pin "1") (pinfunction "1_1") (pintype "passive"))
      (node (ref "R23") (pin "1") (pinfunction "1_1") (pintype "passive"))
    )
    (net (code "55") (name "Net-(D6-K)") (class "Default")
      (node (ref "D6") (pin "2") (pinfunction "K_2") (pintype "passive"))
      (node (ref "F3") (pin "2") (pinfunction "2_2") (pintype "passive"))
      (node (ref "R14") (pin "1") (pinfunction "1_1") (pintype "passive"))
      (node (ref "R24") (pin "1") (pinfunction "1_1") (pintype "passive"))
    )
    (net (code "56") (name "Net-(D7-K)") (class "Default")
      (node (ref "D7") (pin "2") (pinfunction "K_2") (pintype "passive"))
      (node (ref "F4") (pin "2") (pinfunction "2_2") (pintype "passive"))
      (node (ref "R15") (pin "1") (pinfunction "1_1") (pintype "passive"))
      (node (ref "R25") (pin "1") (pinfunction "1_1") (pintype "passive"))
    )
    (net (code "57") (name "Net-(D8-K)") (class "Default")
      (node (ref "D8") (pin "2") (pinfunction "K_2") (pintype "passive"))
      (node (ref "F5") (pin "2") (pinfunction "2_2") (pintype "passive"))
      (node (ref "R16") (pin "1") (pinfunction "1_1") (pintype "passive"))
      (node (ref "R26") (pin "1") (pinfunction "1_1") (pintype "passive"))
    )
    (net (code "58") (name "Net-(D9-K)") (class "Default")
      (node (ref "D9") (pin "2") (pinfunction "K_2") (pintype "passive"))
      (node (ref "F6") (pin "2") (pinfunction "2_2") (pintype "passive"))
      (node (ref "R17") (pin "1") (pinfunction "1_1") (pintype "passive"))
      (node (ref "R27") (pin "1") (pinfunction "1_1") (pintype "passive"))
    )
    (net (code "59") (name "Net-(D10-K)") (class "Default")
      (node (ref "D10") (pin "2") (pinfunction "K_2") (pintype "passive"))
      (node (ref "F7") (pin "2") (pinfunction "2_2") (pintype "passive"))
      (node (ref "R18") (pin "1") (pinfunction "1_1") (pintype "passive"))
      (node (ref "R28") (pin "1") (pinfunction "1_1") (pintype "passive"))
    )
    (net (code "60") (name "Net-(D11-K)") (class "Default")
      (node (ref "D11") (pin "2") (pinfunction "K_2") (pintype "passive"))
      (node (ref "F8") (pin "2") (pinfunction "2_2") (pintype "passive"))
      (node (ref "R19") (pin "1") (pinfunction "1_1") (pintype "passive"))
      (node (ref "R29") (pin "1") (pinfunction "1_1") (pintype "passive"))
    )
    (net (code "61") (name "Net-(D12-K)") (class "Default")
      (node (ref "D12") (pin "2") (pinfunction "K_2") (pintype "passive"))
      (node (ref "F9") (pin "2") (pinfunction "2_2") (pintype "passive"))
      (node (ref "R20") (pin "1") (pinfunction "1_1") (pintype "passive"))
      (node (ref "R30") (pin "1") (pinfunction "1_1") (pintype "passive"))
    )
    (net (code "62") (name "Net-(D13-K)") (class "Default")
      (node (ref "D13") (pin "2") (pinfunction "K_2") (pintype "passive"))
      (node (ref "F10") (pin "2") (pinfunction "2_2") (pintype "passive"))
      (node (ref "R21") (pin "1") (pinfunction "1_1") (pintype "passive"))
      (node (ref "R31") (pin "1") (pinfunction "1_1") (pintype "passive"))
    )
    (net (code "63") (name "Net-(JP1-Pad2)") (class "Default")
      (node (ref "JP1") (pin "2") (pinfunction "2_2") (pintype "passive"))
      (node (ref "R3") (pin "1") (pintype "passive"))
    )
    (net (code "64") (name "Net-(N1-A)") (class "Default")
      (node (ref "C50") (pin "2") (pintype "passive"))
      (node (ref "N1") (pin "2") (pinfunction "A_2") (pintype "passive"))
      (node (ref "R34") (pin "1") (pintype "passive"))
    )
    (net (code "65") (name "Net-(N2-A)") (class "Default")
      (node (ref "C52") (pin "2") (pintype "passive"))
      (node (ref "N2") (pin "2") (pinfunction "A_2") (pintype "passive"))
      (node (ref "R36") (pin "1") (pintype "passive"))
    )
    (net (code "66") (name "Net-(Q1-B)") (class "Default")
      (node (ref "Q1") (pin "1") (pinfunction "B_1") (pintype "passive"))
      (node (ref "R7") (pin "2") (pintype "passive"))
    )
    (net (code "67") (name "Net-(R10-Pad1)") (class "Default")
      (node (ref "R10") (pin "1") (pinfunction "1_1") (pintype "passive"))
      (node (ref "R8") (pin "1") (pinfunction "1_1") (pintype "passive"))
    )
    (net (code "68") (name "Net-(R11-Pad1)") (class "Default")
      (node (ref "R11") (pin "1") (pinfunction "1_1") (pintype "passive"))
      (node (ref "R9") (pin "1") (pinfunction "1_1") (pintype "passive"))
    )
    (net (code "69") (name "Net-(U1-OSC_IN{slash}PD0)") (class "Default")
      (node (ref "C2") (pin "2") (pinfunction "2_2") (pintype "passive"))
      (node (ref "U1") (pin "5") (pinfunction "OSC_IN/PD0_5") (pintype "input"))
      (node (ref "X1") (pin "2") (pinfunction "P2_2") (pintype "passive"))
    )
    (net (code "70") (name "Net-(U1-OSC_OUT{slash}PD1)") (class "Default")
      (node (ref "C3") (pin "2") (pinfunction "2_2") (pintype "passive"))
      (node (ref "U1") (pin "6") (pinfunction "OSC_OUT/PD1_6") (pintype "output"))
      (node (ref "X1") (pin "1") (pinfunction "P1_1") (pintype "passive"))
    )
    (net (code "71") (name "Net-(U2-C1+)") (class "Default")
      (node (ref "C25") (pin "1") (pinfunction "1_1") (pintype "passive"))
      (node (ref "U2") (pin "1") (pinfunction "C1+_1") (pintype "passive"))
    )
    (net (code "72") (name "Net-(U2-C1_)") (class "Default")
      (node (ref "C25") (pin "2") (pinfunction "2_2") (pintype "passive"))
      (node (ref "U2") (pin "3") (pinfunction "C1__3") (pintype "passive"))
    )
    (net (code "73") (name "Net-(U2-C2+)") (class "Default")
      (node (ref "C26") (pin "1") (pinfunction "1_1") (pintype "passive"))
      (node (ref "U2") (pin "4") (pinfunction "C2+_4") (pintype "passive"))
    )
    (net (code "74") (name "Net-(U2-C2_)") (class "Default")
      (node (ref "C26") (pin "2") (pinfunction "2_2") (pintype "passive"))
      (node (ref "U2") (pin "5") (pinfunction "C2__5") (pintype "passive"))
    )
    (net (code "75") (name "Net-(U2-V+)") (class "Default")
      (node (ref "C24") (pin "1") (pinfunction "1_1") (pintype "passive"))
      (node (ref "U2") (pin "2") (pinfunction "V+_2") (pintype "passive"))
    )
    (net (code "76") (name "Net-(U2-V_)") (class "Default")
      (node (ref "C27") (pin "2") (pinfunction "2_2") (pintype "passive"))
      (node (ref "U2") (pin "6") (pinfunction "V__6") (pintype "passive"))
    )
    (net (code "77") (name "unconnected-(J3-Pad14)") (class "Default")
      (node (ref "J3") (pin "14") (pinfunction "14_14") (pintype "passive"))
    )
    (net (code "78") (name "unconnected-(U1-PA1-Pad11)") (class "Default")
      (node (ref "U1") (pin "11") (pinfunction "PA1_11") (pintype "bidirectional"))
    )
    (net (code "79") (name "unconnected-(U1-PA11-Pad32)") (class "Default")
      (node (ref "U1") (pin "32") (pinfunction "PA11_32") (pintype "bidirectional"))
    )
    (net (code "80") (name "unconnected-(U1-PA12-Pad33)") (class "Default")
      (node (ref "U1") (pin "33") (pinfunction "PA12_33") (pintype "bidirectional"))
    )
    (net (code "81") (name "unconnected-(U1-PA15{slash}JTDI-Pad38)") (class "Default")
      (node (ref "U1") (pin "38") (pinfunction "PA15/JTDI_38") (pintype "bidirectional"))
    )
    (net (code "82") (name "unconnected-(U1-PB3{slash}JTDO-Pad39)") (class "Default")
      (node (ref "U1") (pin "39") (pinfunction "PB3/JTDO_39") (pintype "bidirectional+no_connect"))
    )
    (net (code "83") (name "unconnected-(U1-PB4{slash}JNTRST-Pad40)") (class "Default")
      (node (ref "U1") (pin "40") (pinfunction "PB4/JNTRST_40") (pintype "bidirectional+no_connect"))
    )
    (net (code "84") (name "unconnected-(U1-PB5-Pad41)") (class "Default")
      (node (ref "U1") (pin "41") (pinfunction "PB5_41") (pintype "bidirectional+no_connect"))
    )
    (net (code "85") (name "unconnected-(U1-PB6-Pad42)") (class "Default")
      (node (ref "U1") (pin "42") (pinfunction "PB6_42") (pintype "bidirectional+no_connect"))
    )
    (net (code "86") (name "unconnected-(U1-PB7-Pad43)") (class "Default")
      (node (ref "U1") (pin "43") (pinfunction "PB7_43") (pintype "bidirectional+no_connect"))
    )
    (net (code "87") (name "unconnected-(U1-PB8-Pad45)") (class "Default")
      (node (ref "U1") (pin "45") (pinfunction "PB8_45") (pintype "bidirectional+no_connect"))
    )
    (net (code "88") (name "unconnected-(U1-PB9-Pad46)") (class "Default")
      (node (ref "U1") (pin "46") (pinfunction "PB9_46") (pintype "bidirectional+no_connect"))
    )
    (net (code "89") (name "unconnected-(U1-PB10-Pad21)") (class "Default")
      (node (ref "U1") (pin "21") (pinfunction "PB10_21") (pintype "bidirectional"))
    )
    (net (code "90") (name "unconnected-(U1-PB11-Pad22)") (class "Default")
      (node (ref "U1") (pin "22") (pinfunction "PB11_22") (pintype "bidirectional"))
    )
    (net (code "91") (name "unconnected-(U1-PB12-Pad25)") (class "Default")
      (node (ref "U1") (pin "25") (pinfunction "PB12_25") (pintype "bidirectional"))
    )
    (net (code "92") (name "unconnected-(U1-PB13-Pad26)") (class "Default")
      (node (ref "U1") (pin "26") (pinfunction "PB13_26") (pintype "bidirectional"))
    )
    (net (code "93") (name "unconnected-(U1-PB14-Pad27)") (class "Default")
      (node (ref "U1") (pin "27") (pinfunction "PB14_27") (pintype "bidirectional"))
    )
    (net (code "94") (name "unconnected-(U1-PB15-Pad28)") (class "Default")
      (node (ref "U1") (pin "28") (pinfunction "PB15_28") (pintype "bidirectional+no_connect"))
    )
    (net (code "95") (name "unconnected-(U1-PC13-TAMPER-RTC-Pad2)") (class "Default")
      (node (ref "U1") (pin "2") (pinfunction "PC13-TAMPER-RTC_2") (pintype "bidirectional+no_connect"))
    )
    (net (code "96") (name "unconnected-(U1-PC14-OSC32_IN-Pad3)") (class "Default")
      (node (ref "U1") (pin "3") (pinfunction "PC14-OSC32_IN_3") (pintype "bidirectional+no_connect"))
    )
    (net (code "97") (name "unconnected-(U1-PC15-OSC32_OUT-Pad4)") (class "Default")
      (node (ref "U1") (pin "4") (pinfunction "PC15-OSC32_OUT_4") (pintype "bidirectional+no_connect"))
    )
    (net (code "98") (name "unconnected-(U2-R2in-Pad8)") (class "Default")
      (node (ref "U2") (pin "8") (pinfunction "R2in_8") (pintype "passive"))
    )
    (net (code "99") (name "unconnected-(U2-R2out-Pad9)") (class "Default")
      (node (ref "U2") (pin "9") (pinfunction "R2out_9") (pintype "passive"))
    )
    (net (code "100") (name "unconnected-(U2-T2in-Pad10)") (class "Default")
      (node (ref "U2") (pin "10") (pinfunction "T2in_10") (pintype "passive"))
    )
    (net (code "101") (name "unconnected-(U2-T2out-Pad7)") (class "Default")
      (node (ref "U2") (pin "7") (pinfunction "T2out_7") (pintype "passive"))
    )
    (net (code "102") (name "unconnected-(U3-A-Pad6)") (class "Default")
      (node (ref "U3") (pin "6") (pinfunction "A_6") (pintype "tri_state"))
    )
    (net (code "103") (name "unconnected-(U3-B-Pad7)") (class "Default")
      (node (ref "U3") (pin "7") (pinfunction "B_7") (pintype "tri_state"))
    )
    (net (code "104") (name "unconnected-(U7-NC-Pad7)") (class "Default")
      (node (ref "U7") (pin "7") (pinfunction "NC_7") (pintype "passive+no_connect"))
    )
    (net (code "105") (name "unconnected-(U7-NC-Pad8)") (class "Default")
      (node (ref "U7") (pin "8") (pinfunction "NC_8") (pintype "passive+no_connect"))
    )
    (net (code "106") (name "unconnected-(U7-TP-Pad1)") (class "Default")
      (node (ref "U7") (pin "1") (pinfunction "TP_1") (pintype "passive+no_connect"))
    )
    (net (code "107") (name "unconnected-(U7-TP-Pad5)") (class "Default")
      (node (ref "U7") (pin "5") (pinfunction "TP_5") (pintype "passive+no_connect"))
    )
  )
)
